# Schematic.net
KiCad netlist of a schematic drawn in EAGLE
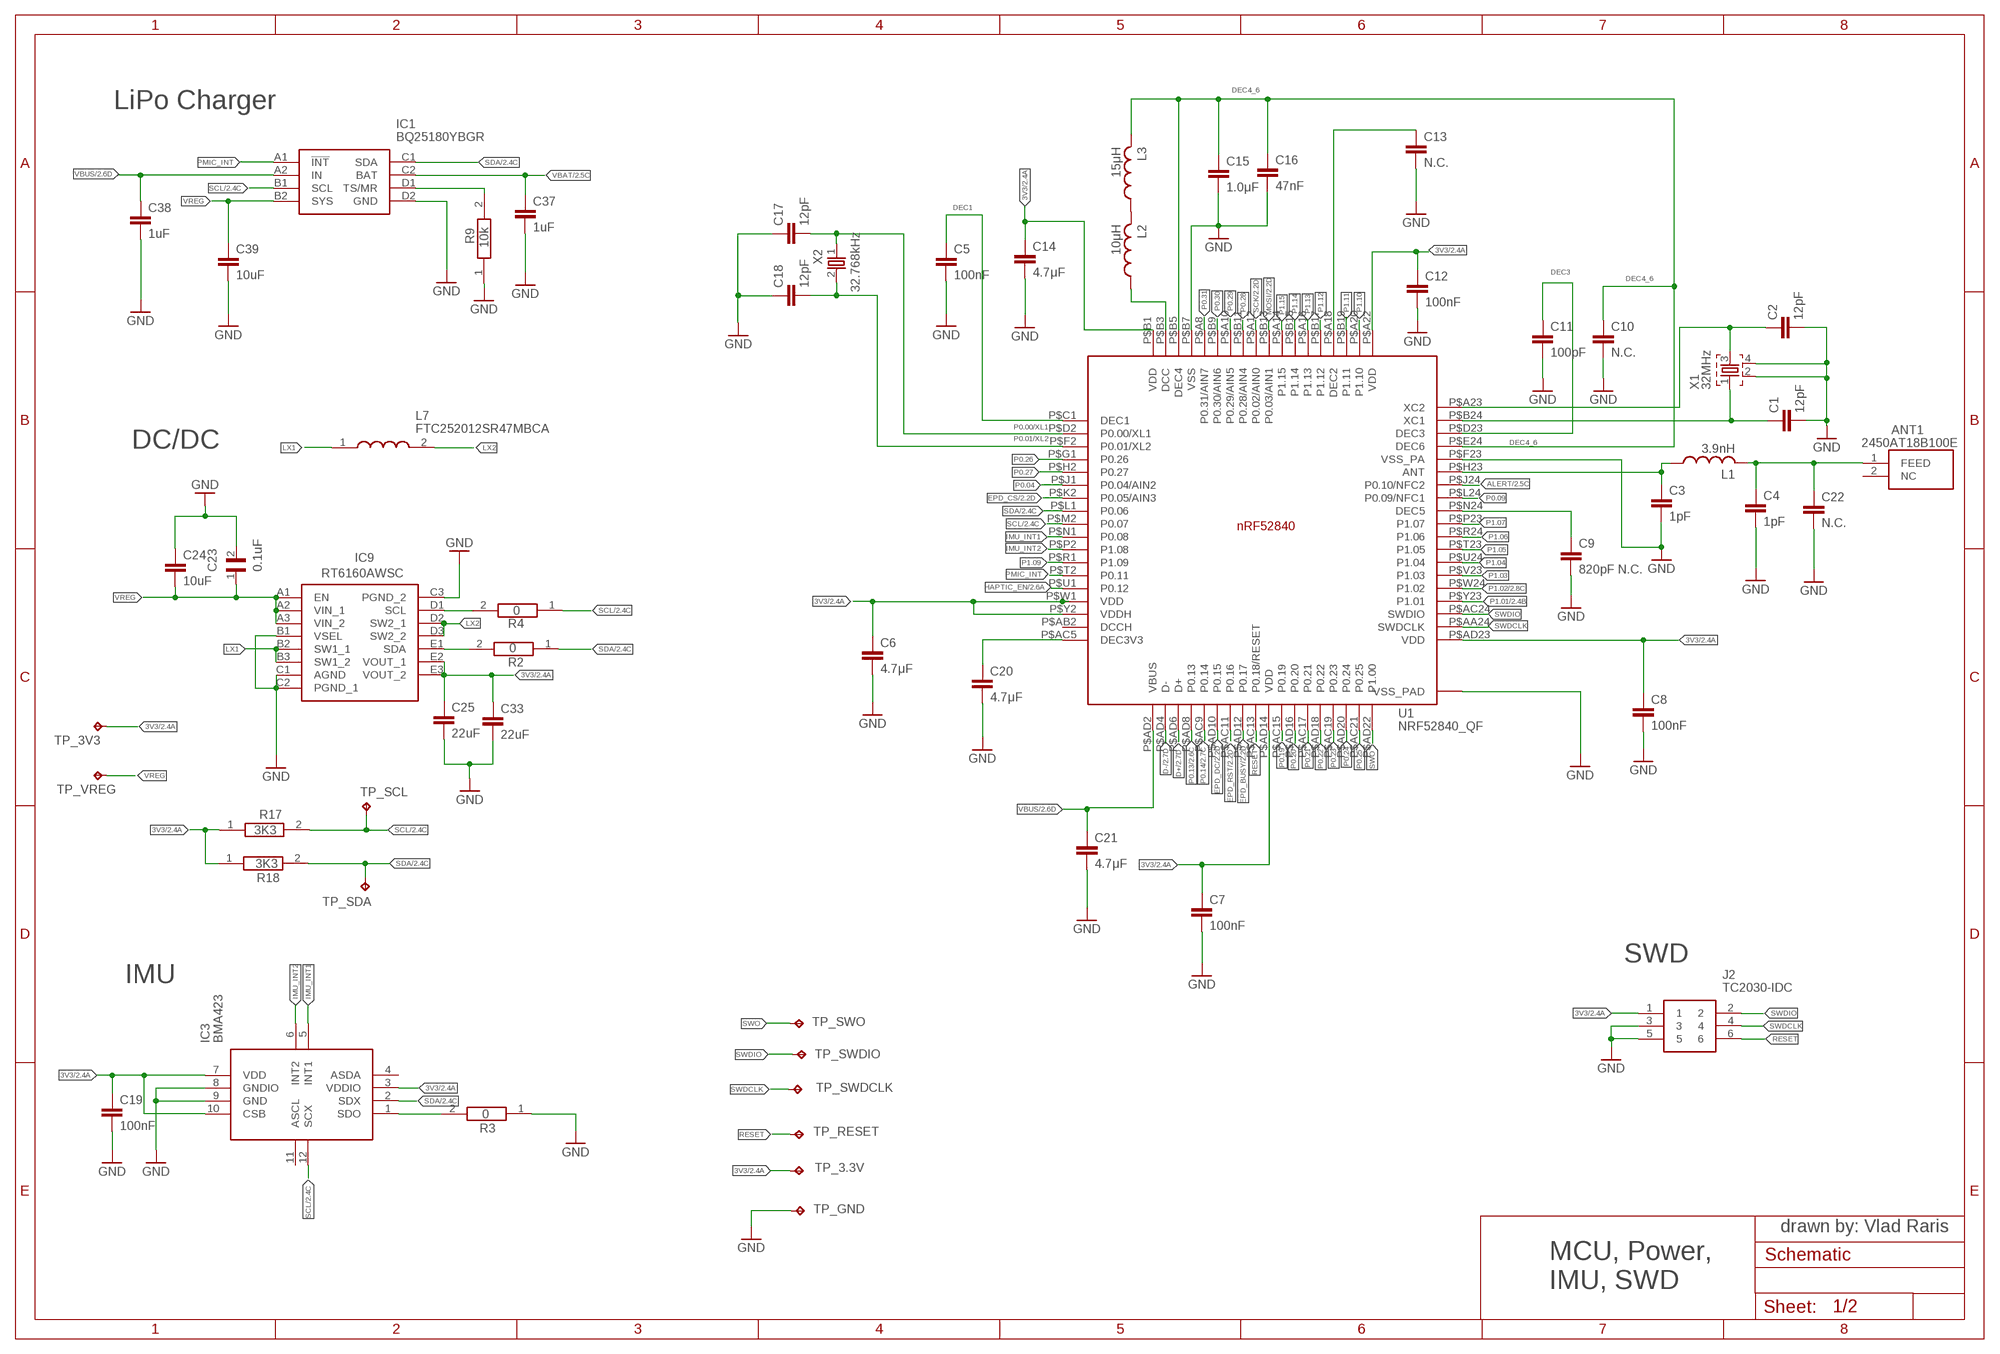
[diagram p0: schematic, sheet 1]
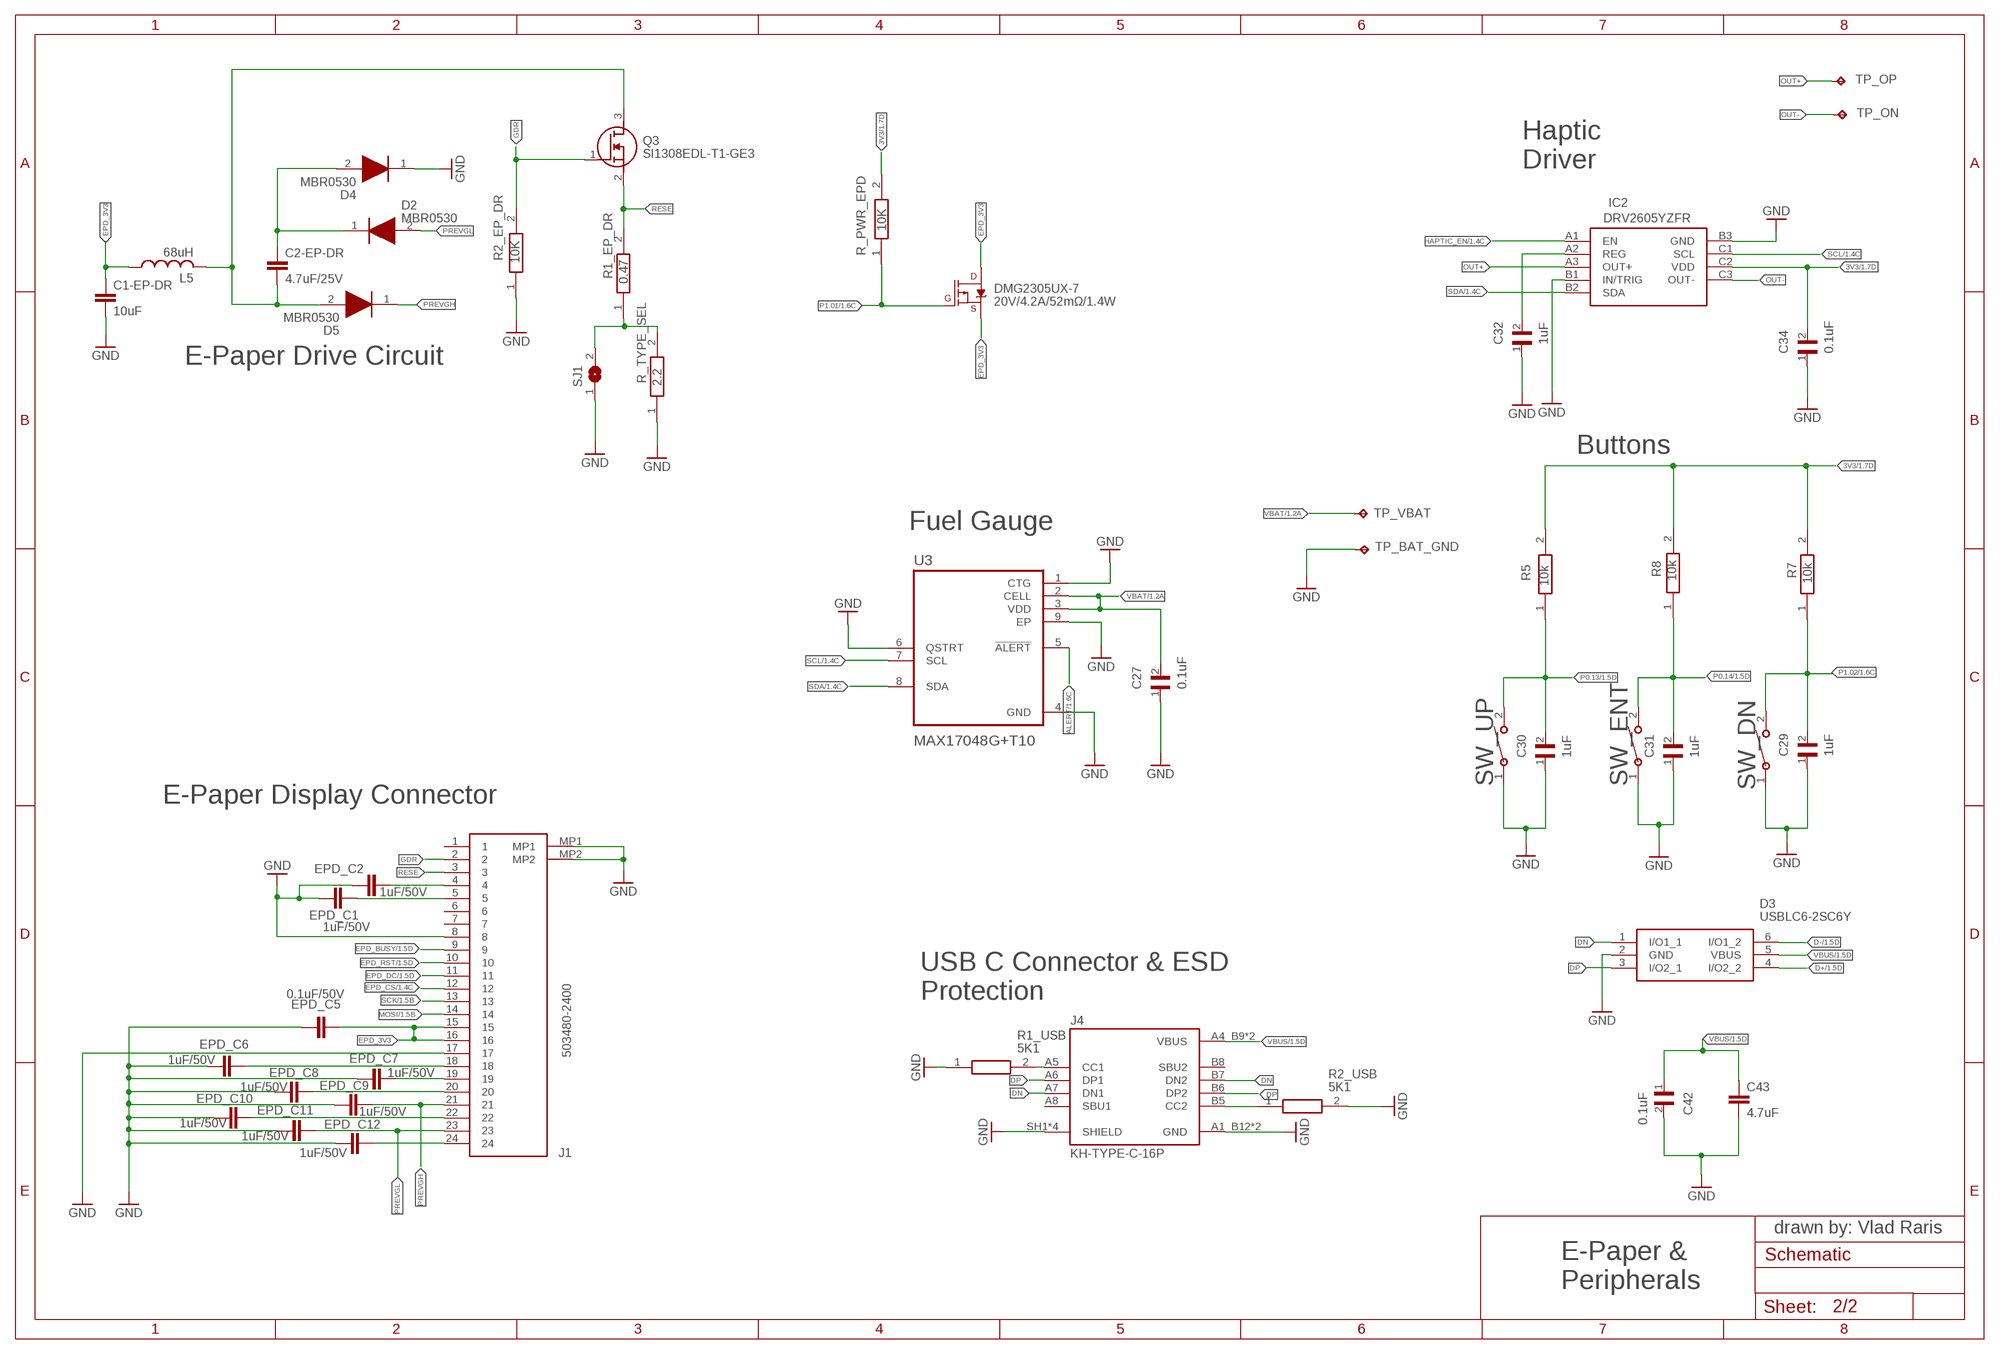
[diagram p1: schematic, sheet 2]

(export (version "E")
  (design (tool "Eeschema 10.0.6"))
  (components
    (comp (ref "C1-EP-DR")
      (value "10uF")
      (footprint "eagle-import:NORDIC_NRF_3_RESC0201_L")
      (libsource (lib "eagle-import") (part "NORDIC_NRF_3_CAPACITOR_0201_L"))
    )
    (comp (ref "C2-EP-DR")
      (value "4.7uF/25V")
      (footprint "eagle-import:PERFECT_0402_0402")
      (libsource (lib "eagle-import") (part "PERFECT_0402_CAP_0402"))
    )
    (comp (ref "C27")
      (value "0.1uF")
      (footprint "eagle-import:GRM011R60J152KE01L_2_CAPC0201X13N")
      (fields (field (name "MF") "Murata") (field (name "MP") "GRM011R60J152KE01L"))
      (libsource (lib "eagle-import") (part "GRM011R60J152KE01L_2_GRM011R60J152KE01L"))
    )
    (comp (ref "C29")
      (value "1uF")
      (footprint "eagle-import:GRM011R60J152KE01L_2_CAPC0201X13N")
      (fields (field (name "MF") "Murata") (field (name "MP") "GRM011R60J152KE01L"))
      (libsource (lib "eagle-import") (part "GRM011R60J152KE01L_2_GRM011R60J152KE01L"))
    )
    (comp (ref "C30")
      (value "1uF")
      (footprint "eagle-import:GRM011R60J152KE01L_2_CAPC0201X13N")
      (fields (field (name "MF") "Murata") (field (name "MP") "GRM011R60J152KE01L"))
      (libsource (lib "eagle-import") (part "GRM011R60J152KE01L_2_GRM011R60J152KE01L"))
    )
    (comp (ref "C31")
      (value "1uF")
      (footprint "eagle-import:GRM011R60J152KE01L_2_CAPC0201X13N")
      (fields (field (name "MF") "Murata") (field (name "MP") "GRM011R60J152KE01L"))
      (libsource (lib "eagle-import") (part "GRM011R60J152KE01L_2_GRM011R60J152KE01L"))
    )
    (comp (ref "C32")
      (value "1uF")
      (footprint "eagle-import:GRM011R60J152KE01L_2_CAPC0201X13N")
      (fields (field (name "MF") "Murata") (field (name "MP") "GRM011R60J152KE01L"))
      (libsource (lib "eagle-import") (part "GRM011R60J152KE01L_2_GRM011R60J152KE01L"))
    )
    (comp (ref "C34")
      (value "0.1uF")
      (footprint "eagle-import:GRM011R60J152KE01L_2_CAPC0201X13N")
      (fields (field (name "MF") "Murata") (field (name "MP") "GRM011R60J152KE01L"))
      (libsource (lib "eagle-import") (part "GRM011R60J152KE01L_2_GRM011R60J152KE01L"))
    )
    (comp (ref "C42")
      (value "0.1uF")
      (footprint "eagle-import:GRM011R60J152KE01L_2_CAPC0201X13N")
      (fields (field (name "MF") "Murata") (field (name "MP") "GRM011R60J152KE01L"))
      (libsource (lib "eagle-import") (part "GRM011R60J152KE01L_2_GRM011R60J152KE01L"))
    )
    (comp (ref "C43")
      (value "4.7uF")
      (footprint "eagle-import:PERFECT_0402_0402")
      (libsource (lib "eagle-import") (part "PERFECT_0402_CAP_0402"))
    )
    (comp (ref "D2")
      (value "MBR0530")
      (footprint "eagle-import:ESP32_C6_LIBRARY_5_SOD3716X135N")
      (fields (field (name "MF") "ON Semiconductor"))
      (libsource (lib "eagle-import") (part "ESP32_C6_LIBRARY_5_MBR0530"))
    )
    (comp (ref "D3")
      (value "USBLC6-2SC6Y")
      (footprint "eagle-import:ESP32_C6_LIBRARY_3_SOT95P280X145-6N")
      (fields (field (name "MF") "STMicroelectronics"))
      (libsource (lib "eagle-import") (part "ESP32_C6_LIBRARY_3_USBLC6-2SC6Y"))
    )
    (comp (ref "D4")
      (value "MBR0530")
      (footprint "eagle-import:ESP32_C6_LIBRARY_5_SOD3716X135N")
      (fields (field (name "MF") "ON Semiconductor"))
      (libsource (lib "eagle-import") (part "ESP32_C6_LIBRARY_5_MBR0530"))
    )
    (comp (ref "D5")
      (value "MBR0530")
      (footprint "eagle-import:ESP32_C6_LIBRARY_5_SOD3716X135N")
      (fields (field (name "MF") "ON Semiconductor"))
      (libsource (lib "eagle-import") (part "ESP32_C6_LIBRARY_5_MBR0530"))
    )
    (comp (ref "DMG2305UX-7")
      (value "20V/4.2A/52mΩ/1.4W")
      (footprint "eagle-import:ESP32_C6_LIBRARY_4_ESP32_C6_LIBRARY_4_ESP32_C6_LIBRARY_4_ESP32_C6_LIBRARY_4_ESP32_WROVER_SPARKFUN-DISCRETESEMI_SOT23-3")
      (libsource (lib "eagle-import") (part "ESP32_C6_LIBRARY_4_ESP32_WROVER_SPARKFUN-DISCRETESEMI_MOSFET_PCH-DMG2305UX-7"))
    )
    (comp (ref "EPD_C1")
      (value "1uF/50V")
      (footprint "eagle-import:PERFECT_0402_0402")
      (libsource (lib "eagle-import") (part "PERFECT_0402_CAP_0402"))
    )
    (comp (ref "EPD_C2")
      (value "1uF/50V")
      (footprint "eagle-import:PERFECT_0402_0402")
      (libsource (lib "eagle-import") (part "PERFECT_0402_CAP_0402"))
    )
    (comp (ref "EPD_C5")
      (value "0.1uF/50V")
      (footprint "eagle-import:PERFECT_0402_0402")
      (libsource (lib "eagle-import") (part "PERFECT_0402_CAP_0402"))
    )
    (comp (ref "EPD_C6")
      (value "1uF/50V")
      (footprint "eagle-import:PERFECT_0402_0402")
      (libsource (lib "eagle-import") (part "PERFECT_0402_CAP_0402"))
    )
    (comp (ref "EPD_C7")
      (value "1uF/50V")
      (footprint "eagle-import:PERFECT_0402_0402")
      (libsource (lib "eagle-import") (part "PERFECT_0402_CAP_0402"))
    )
    (comp (ref "EPD_C8")
      (value "1uF/50V")
      (footprint "eagle-import:PERFECT_0402_0402")
      (libsource (lib "eagle-import") (part "PERFECT_0402_CAP_0402"))
    )
    (comp (ref "EPD_C9")
      (value "1uF/50V")
      (footprint "eagle-import:PERFECT_0402_0402")
      (libsource (lib "eagle-import") (part "PERFECT_0402_CAP_0402"))
    )
    (comp (ref "EPD_C10")
      (value "1uF/50V")
      (footprint "eagle-import:PERFECT_0402_0402")
      (libsource (lib "eagle-import") (part "PERFECT_0402_CAP_0402"))
    )
    (comp (ref "EPD_C11")
      (value "1uF/50V")
      (footprint "eagle-import:PERFECT_0402_0402")
      (libsource (lib "eagle-import") (part "PERFECT_0402_CAP_0402"))
    )
    (comp (ref "EPD_C12")
      (value "1uF/50V")
      (footprint "eagle-import:PERFECT_0402_0402")
      (libsource (lib "eagle-import") (part "PERFECT_0402_CAP_0402"))
    )
    (comp (ref "IC2")
      (value "DRV2605YZFR")
      (footprint "eagle-import:DRV2605YZFR_BGA9C50P3X3_144X144X62")
      (libsource (lib "eagle-import") (part "DRV2605YZFR_DRV2605YZFR"))
    )
    (comp (ref "J1")
      (value "503480-2400")
      (footprint "eagle-import:503480-2400_5034802400")
      (fields (field (name "MOUSER_PART_NUMBER") "538-503480-2400"))
      (libsource (lib "eagle-import") (part "503480-2400_503480-2400"))
    )
    (comp (ref "J4")
      (value "KH-TYPE-C-16P")
      (footprint "eagle-import:KH-TYPE-C-16P_KINGHELM_KH-TYPE-C-16P")
      (fields (field (name "MF") "kinghelm"))
      (libsource (lib "eagle-import") (part "KH-TYPE-C-16P_KH-TYPE-C-16P"))
    )
    (comp (ref "L5")
      (value "68uH")
      (footprint "eagle-import:NORDIC_NRF_2_RESC0402_L")
      (libsource (lib "eagle-import") (part "NORDIC_NRF_2_INDUCTOR_0402_L"))
    )
    (comp (ref "Q3")
      (value "SI1308EDL-T1-GE3")
      (footprint "eagle-import:ESP32_C6_LIBRARY_6_SOT65P210X110-3N")
      (fields (field (name "MF") "Vishay Siliconix"))
      (libsource (lib "eagle-import") (part "ESP32_C6_LIBRARY_6_SI1308EDL-T1-GE3"))
    )
    (comp (ref "R1_EP_DR")
      (value "0.47")
      (footprint "eagle-import:CPF0201D7K68C1_0201")
      (libsource (lib "eagle-import") (part "CPF0201D7K68C1_CPF0201D7K68C1"))
    )
    (comp (ref "R1_USB")
      (value "5K1")
      (footprint "eagle-import:CPF0201D7K68C1_0201")
      (libsource (lib "eagle-import") (part "CPF0201D7K68C1_CPF0201D7K68C1"))
    )
    (comp (ref "R2_EP_DR")
      (value "10K")
      (footprint "eagle-import:CPF0201D7K68C1_0201")
      (libsource (lib "eagle-import") (part "CPF0201D7K68C1_CPF0201D7K68C1"))
    )
    (comp (ref "R2_USB")
      (value "5K1")
      (footprint "eagle-import:CPF0201D7K68C1_0201")
      (libsource (lib "eagle-import") (part "CPF0201D7K68C1_CPF0201D7K68C1"))
    )
    (comp (ref "R5")
      (value "10k")
      (footprint "eagle-import:CPF0201D7K68C1_0201")
      (libsource (lib "eagle-import") (part "CPF0201D7K68C1_CPF0201D7K68C1"))
    )
    (comp (ref "R7")
      (value "10k")
      (footprint "eagle-import:CPF0201D7K68C1_0201")
      (libsource (lib "eagle-import") (part "CPF0201D7K68C1_CPF0201D7K68C1"))
    )
    (comp (ref "R8")
      (value "10k")
      (footprint "eagle-import:CPF0201D7K68C1_0201")
      (libsource (lib "eagle-import") (part "CPF0201D7K68C1_CPF0201D7K68C1"))
    )
    (comp (ref "R_PWR_EPD")
      (value "10K")
      (footprint "eagle-import:CPF0201D7K68C1_0201")
      (libsource (lib "eagle-import") (part "CPF0201D7K68C1_CPF0201D7K68C1"))
    )
    (comp (ref "R_TYPE_SEL")
      (value "2.2")
      (footprint "eagle-import:CPF0201D7K68C1_0201")
      (libsource (lib "eagle-import") (part "CPF0201D7K68C1_CPF0201D7K68C1"))
    )
    (comp (ref "SJ1")
      (value "ESP32_C6_LIBRARY_7_JUMPER_SJ")
      (footprint "eagle-import:ESP32_C6_LIBRARY_7_JUMPER_SJ")
      (libsource (lib "eagle-import") (part "ESP32_C6_LIBRARY_7_JUMPER_SJ"))
    )
    (comp (ref "SW_DN")
      (value "2025-10-22_07-23-44_LIBRARY_EVP-AKE31ASW_EVP-AKE31A_PAN")
      (footprint "eagle-import:2025-10-22_07-23-44_LIBRARY_SW_EVP-AKE31A_PAN")
      (fields
        (field (name "MANUFACTURER_PART_NUMBER") "EVP-AKE31A")
        (field (name "COPYRIGHT") "Copyright (C) 2025 Ultra Librarian. All rights reserved.")
      )
      (libsource (lib "eagle-import") (part "2025-10-22_07-23-44_LIBRARY_EVP-AKE31ASW_EVP-AKE31A_PAN"))
    )
    (comp (ref "SW_ENT")
      (value "2025-10-22_07-23-44_LIBRARY_EVP-AKE31ASW_EVP-AKE31A_PAN")
      (footprint "eagle-import:2025-10-22_07-23-44_LIBRARY_SW_EVP-AKE31A_PAN")
      (fields
        (field (name "MANUFACTURER_PART_NUMBER") "EVP-AKE31A")
        (field (name "COPYRIGHT") "Copyright (C) 2025 Ultra Librarian. All rights reserved.")
      )
      (libsource (lib "eagle-import") (part "2025-10-22_07-23-44_LIBRARY_EVP-AKE31ASW_EVP-AKE31A_PAN"))
    )
    (comp (ref "SW_UP")
      (value "2025-10-22_07-23-44_LIBRARY_EVP-AKE31ASW_EVP-AKE31A_PAN")
      (footprint "eagle-import:2025-10-22_07-23-44_LIBRARY_SW_EVP-AKE31A_PAN")
      (fields
        (field (name "MANUFACTURER_PART_NUMBER") "EVP-AKE31A")
        (field (name "COPYRIGHT") "Copyright (C) 2025 Ultra Librarian. All rights reserved.")
      )
      (libsource (lib "eagle-import") (part "2025-10-22_07-23-44_LIBRARY_EVP-AKE31ASW_EVP-AKE31A_PAN"))
    )
    (comp (ref "TP_BAT_GND")
      (value "HECTOR_WATCH_1_TPTP20R")
      (footprint "eagle-import:HECTOR_WATCH_1_TP20R")
      (libsource (lib "eagle-import") (part "HECTOR_WATCH_1_TPTP20R"))
    )
    (comp (ref "TP_ON")
      (value "HECTOR_WATCH_1_TPTP20R")
      (footprint "eagle-import:HECTOR_WATCH_1_TP20R")
      (libsource (lib "eagle-import") (part "HECTOR_WATCH_1_TPTP20R"))
    )
    (comp (ref "TP_OP")
      (value "HECTOR_WATCH_1_TPTP20R")
      (footprint "eagle-import:HECTOR_WATCH_1_TP20R")
      (libsource (lib "eagle-import") (part "HECTOR_WATCH_1_TPTP20R"))
    )
    (comp (ref "TP_VBAT")
      (value "HECTOR_WATCH_1_TPTP20R")
      (footprint "eagle-import:HECTOR_WATCH_1_TP20R")
      (libsource (lib "eagle-import") (part "HECTOR_WATCH_1_TPTP20R"))
    )
    (comp (ref "U3")
      (value "MAX17048G+T10")
      (footprint "eagle-import:ESP32_C6_LIBRARY_SON50P200X200X80-9N")
      (fields (field (name "MF") "Analog Devices"))
      (libsource (lib "eagle-import") (part "ESP32_C6_LIBRARY_MAX17048G+T10"))
    )
    (comp (ref "ANT1")
      (value "2450AT18B100E")
      (footprint "eagle-import:2450AT18B100E_ANTC3216X140N")
      (fields (field (name "MOUSER_PART_NUMBER") "609-2450AT18B100E"))
      (libsource (lib "eagle-import") (part "2450AT18B100E_2450AT18B100E"))
    )
    (comp (ref "C1")
      (value "12pF")
      (footprint "eagle-import:NORDIC_NRF_3_RESC0201_L")
      (libsource (lib "eagle-import") (part "NORDIC_NRF_3_CAPACITOR_0201_L"))
    )
    (comp (ref "C2")
      (value "12pF")
      (footprint "eagle-import:NORDIC_NRF_3_RESC0201_L")
      (libsource (lib "eagle-import") (part "NORDIC_NRF_3_CAPACITOR_0201_L"))
    )
    (comp (ref "C3")
      (value "1pF")
      (footprint "eagle-import:NORDIC_NRF_3_RESC0201_L")
      (libsource (lib "eagle-import") (part "NORDIC_NRF_3_CAPACITOR_0201_L"))
    )
    (comp (ref "C4")
      (value "1pF")
      (footprint "eagle-import:NORDIC_NRF_3_RESC0201_L")
      (libsource (lib "eagle-import") (part "NORDIC_NRF_3_CAPACITOR_0201_L"))
    )
    (comp (ref "C5")
      (value "100nF")
      (footprint "eagle-import:NORDIC_NRF_3_RESC0201_L")
      (libsource (lib "eagle-import") (part "NORDIC_NRF_3_CAPACITOR_0201_L"))
    )
    (comp (ref "C6")
      (value "4.7μF")
      (footprint "eagle-import:PERFECT_0402_0402")
      (libsource (lib "eagle-import") (part "PERFECT_0402_CAP_0402"))
    )
    (comp (ref "C7")
      (value "100nF")
      (footprint "eagle-import:NORDIC_NRF_3_RESC0201_L")
      (libsource (lib "eagle-import") (part "NORDIC_NRF_3_CAPACITOR_0201_L"))
    )
    (comp (ref "C8")
      (value "100nF")
      (footprint "eagle-import:NORDIC_NRF_3_RESC0201_L")
      (libsource (lib "eagle-import") (part "NORDIC_NRF_3_CAPACITOR_0201_L"))
    )
    (comp (ref "C9")
      (value "820pF N.C.")
      (footprint "eagle-import:NORDIC_NRF_3_RESC0201_L")
      (libsource (lib "eagle-import") (part "NORDIC_NRF_3_CAPACITOR_0201_L"))
    )
    (comp (ref "C10")
      (value "N.C.")
      (footprint "eagle-import:NORDIC_NRF_3_RESC0201_L")
      (libsource (lib "eagle-import") (part "NORDIC_NRF_3_CAPACITOR_0201_L"))
    )
    (comp (ref "C11")
      (value "100pF")
      (footprint "eagle-import:NORDIC_NRF_3_RESC0201_L")
      (libsource (lib "eagle-import") (part "NORDIC_NRF_3_CAPACITOR_0201_L"))
    )
    (comp (ref "C12")
      (value "100nF")
      (footprint "eagle-import:NORDIC_NRF_3_RESC0201_L")
      (libsource (lib "eagle-import") (part "NORDIC_NRF_3_CAPACITOR_0201_L"))
    )
    (comp (ref "C13")
      (value "N.C.")
      (footprint "eagle-import:NORDIC_NRF_3_RESC0201_L")
      (libsource (lib "eagle-import") (part "NORDIC_NRF_3_CAPACITOR_0201_L"))
    )
    (comp (ref "C14")
      (value "4.7μF")
      (footprint "eagle-import:PERFECT_0402_0402")
      (libsource (lib "eagle-import") (part "PERFECT_0402_CAP_0402"))
    )
    (comp (ref "C15")
      (value "1.0μF")
      (footprint "eagle-import:PERFECT_0402_0402")
      (libsource (lib "eagle-import") (part "PERFECT_0402_CAP_0402"))
    )
    (comp (ref "C16")
      (value "47nF")
      (footprint "eagle-import:NORDIC_NRF_3_RESC0201_L")
      (libsource (lib "eagle-import") (part "NORDIC_NRF_3_CAPACITOR_0201_L"))
    )
    (comp (ref "C17")
      (value "12pF")
      (footprint "eagle-import:NORDIC_NRF_3_RESC0201_L")
      (libsource (lib "eagle-import") (part "NORDIC_NRF_3_CAPACITOR_0201_L"))
    )
    (comp (ref "C18")
      (value "12pF")
      (footprint "eagle-import:NORDIC_NRF_3_RESC0201_L")
      (libsource (lib "eagle-import") (part "NORDIC_NRF_3_CAPACITOR_0201_L"))
    )
    (comp (ref "C19")
      (value "100nF")
      (footprint "eagle-import:PERFECT_0402_0402")
      (libsource (lib "eagle-import") (part "PERFECT_0402_CAP_0402"))
    )
    (comp (ref "C20")
      (value "4.7μF")
      (footprint "eagle-import:PERFECT_0402_0402")
      (libsource (lib "eagle-import") (part "PERFECT_0402_CAP_0402"))
    )
    (comp (ref "C21")
      (value "4.7μF")
      (footprint "eagle-import:PERFECT_0402_0402")
      (libsource (lib "eagle-import") (part "PERFECT_0402_CAP_0402"))
    )
    (comp (ref "C22")
      (value "N.C.")
      (footprint "eagle-import:NORDIC_NRF_3_RESC0201_L")
      (libsource (lib "eagle-import") (part "NORDIC_NRF_3_CAPACITOR_0201_L"))
    )
    (comp (ref "C23")
      (value "0.1uF")
      (footprint "eagle-import:GRM011R60J152KE01L_1_0201")
      (libsource (lib "eagle-import") (part "GRM011R60J152KE01L_1_GRM011R60J152KE01L"))
    )
    (comp (ref "C24")
      (value "10uF")
      (footprint "eagle-import:PERFECT_0402_0402")
      (libsource (lib "eagle-import") (part "PERFECT_0402_CAP_0402"))
    )
    (comp (ref "C25")
      (value "22uF")
      (footprint "eagle-import:PERFECT_0402_0402")
      (libsource (lib "eagle-import") (part "PERFECT_0402_CAP_0402"))
    )
    (comp (ref "C33")
      (value "22uF")
      (footprint "eagle-import:PERFECT_0402_0402")
      (libsource (lib "eagle-import") (part "PERFECT_0402_CAP_0402"))
    )
    (comp (ref "C37")
      (value "1uF")
      (footprint "eagle-import:PERFECT_0402_0402")
      (libsource (lib "eagle-import") (part "PERFECT_0402_CAP_0402"))
    )
    (comp (ref "C38")
      (value "1uF")
      (footprint "eagle-import:PERFECT_0402_0402")
      (libsource (lib "eagle-import") (part "PERFECT_0402_CAP_0402"))
    )
    (comp (ref "C39")
      (value "10uF")
      (footprint "eagle-import:PERFECT_0402_0402")
      (libsource (lib "eagle-import") (part "PERFECT_0402_CAP_0402"))
    )
    (comp (ref "IC1")
      (value "BQ25180YBGR")
      (footprint "eagle-import:BQ25180YBGR_BGA8C40P2X4_100X155X50")
      (fields (field (name "MOUSER_PART_NUMBER") "595-BQ25180YBGR"))
      (libsource (lib "eagle-import") (part "BQ25180YBGR_BQ25180YBGR"))
    )
    (comp (ref "IC3")
      (value "BMA423")
      (footprint "eagle-import:BMA423_BMA423")
      (fields (field (name "MOUSER_PART_NUMBER") "262-BMA423"))
      (libsource (lib "eagle-import") (part "BMA423_BMA423"))
    )
    (comp (ref "IC9")
      (value "RT6160AWSC")
      (footprint "eagle-import:RT6160AWSC_BGA15C40P3X5_140X230X60")
      (fields (field (name "MOUSER_PART_NUMBER") "835-RT6160AWSC"))
      (libsource (lib "eagle-import") (part "RT6160AWSC_RT6160AWSC"))
    )
    (comp (ref "J2")
      (value "TC2030-IDC")
      (footprint "eagle-import:TC2030-IDC_TC2030IDC")
      (libsource (lib "eagle-import") (part "TC2030-IDC_TC2030-IDC"))
    )
    (comp (ref "L1")
      (value "3.9nH")
      (footprint "eagle-import:NORDIC_NRF_2_RESC0402_L")
      (libsource (lib "eagle-import") (part "NORDIC_NRF_2_INDUCTOR_0402_L"))
    )
    (comp (ref "L2")
      (value "10μH")
      (footprint "eagle-import:NORDIC_NRF_2_RESC0402_L")
      (libsource (lib "eagle-import") (part "NORDIC_NRF_2_INDUCTOR_0402_L"))
    )
    (comp (ref "L3")
      (value "15μH")
      (footprint "eagle-import:NORDIC_NRF_2_RESC0402_L")
      (libsource (lib "eagle-import") (part "NORDIC_NRF_2_INDUCTOR_0402_L"))
    )
    (comp (ref "L7")
      (value "FTC252012SR47MBCA")
      (footprint "eagle-import:MLP2016SR47MT0S1_INDC2016X100N")
      (libsource (lib "eagle-import") (part "MLP2016SR47MT0S1_FTC252012SR47MBCA"))
    )
    (comp (ref "R2")
      (value "0")
      (footprint "eagle-import:CPF0201D7K68C1_0201")
      (libsource (lib "eagle-import") (part "CPF0201D7K68C1_CPF0201D7K68C1"))
    )
    (comp (ref "R3")
      (value "0")
      (footprint "eagle-import:CPF0201D7K68C1_0201")
      (libsource (lib "eagle-import") (part "CPF0201D7K68C1_CPF0201D7K68C1"))
    )
    (comp (ref "R4")
      (value "0")
      (footprint "eagle-import:CPF0201D7K68C1_0201")
      (libsource (lib "eagle-import") (part "CPF0201D7K68C1_CPF0201D7K68C1"))
    )
    (comp (ref "R9")
      (value "10k")
      (footprint "eagle-import:CPF0201D7K68C1_0201")
      (libsource (lib "eagle-import") (part "CPF0201D7K68C1_CPF0201D7K68C1"))
    )
    (comp (ref "R17")
      (value "3K3")
      (footprint "eagle-import:CPF0201D7K68C1_0201")
      (libsource (lib "eagle-import") (part "CPF0201D7K68C1_CPF0201D7K68C1"))
    )
    (comp (ref "R18")
      (value "3K3")
      (footprint "eagle-import:CPF0201D7K68C1_0201")
      (libsource (lib "eagle-import") (part "CPF0201D7K68C1_CPF0201D7K68C1"))
    )
    (comp (ref "TP_3.3V")
      (value "HECTOR_WATCH_1_TPTP20R")
      (footprint "eagle-import:HECTOR_WATCH_1_TP20R")
      (libsource (lib "eagle-import") (part "HECTOR_WATCH_1_TPTP20R"))
    )
    (comp (ref "TP_3V3")
      (value "HECTOR_WATCH_1_TPTP20R")
      (footprint "eagle-import:HECTOR_WATCH_1_TP20R")
      (libsource (lib "eagle-import") (part "HECTOR_WATCH_1_TPTP20R"))
    )
    (comp (ref "TP_GND")
      (value "HECTOR_WATCH_1_TPTP20R")
      (footprint "eagle-import:HECTOR_WATCH_1_TP20R")
      (libsource (lib "eagle-import") (part "HECTOR_WATCH_1_TPTP20R"))
    )
    (comp (ref "TP_RESET")
      (value "HECTOR_WATCH_1_TPTP20R")
      (footprint "eagle-import:HECTOR_WATCH_1_TP20R")
      (libsource (lib "eagle-import") (part "HECTOR_WATCH_1_TPTP20R"))
    )
    (comp (ref "TP_SCL")
      (value "HECTOR_WATCH_1_TPTP20R")
      (footprint "eagle-import:HECTOR_WATCH_1_TP20R")
      (libsource (lib "eagle-import") (part "HECTOR_WATCH_1_TPTP20R"))
    )
    (comp (ref "TP_SDA")
      (value "HECTOR_WATCH_1_TPTP20R")
      (footprint "eagle-import:HECTOR_WATCH_1_TP20R")
      (libsource (lib "eagle-import") (part "HECTOR_WATCH_1_TPTP20R"))
    )
    (comp (ref "TP_SWDCLK")
      (value "HECTOR_WATCH_1_TPTP20R")
      (footprint "eagle-import:HECTOR_WATCH_1_TP20R")
      (libsource (lib "eagle-import") (part "HECTOR_WATCH_1_TPTP20R"))
    )
    (comp (ref "TP_SWDIO")
      (value "HECTOR_WATCH_1_TPTP20R")
      (footprint "eagle-import:HECTOR_WATCH_1_TP20R")
      (libsource (lib "eagle-import") (part "HECTOR_WATCH_1_TPTP20R"))
    )
    (comp (ref "TP_SWO")
      (value "HECTOR_WATCH_1_TPTP20R")
      (footprint "eagle-import:HECTOR_WATCH_1_TP20R")
      (libsource (lib "eagle-import") (part "HECTOR_WATCH_1_TPTP20R"))
    )
    (comp (ref "TP_VREG")
      (value "HECTOR_WATCH_1_TPTP20R")
      (footprint "eagle-import:HECTOR_WATCH_1_TP20R")
      (libsource (lib "eagle-import") (part "HECTOR_WATCH_1_TPTP20R"))
    )
    (comp (ref "U1")
      (value "NRF52840_QF")
      (footprint "eagle-import:NORDIC_NRF_4_AQFN50P700X700X85_HS-74N")
      (libsource (lib "eagle-import") (part "NORDIC_NRF_4_NRF52840_QF"))
    )
    (comp (ref "X1")
      (value "32MHz")
      (footprint "eagle-import:NORDIC_NRF_BT-XTAL_2016_N")
      (libsource (lib "eagle-import") (part "NORDIC_NRF_XTAL_32MHZ"))
    )
    (comp (ref "X2")
      (value "32.768kHz")
      (footprint "eagle-import:NORDIC_NRF_1_XTAL_3215_N")
      (libsource (lib "eagle-import") (part "NORDIC_NRF_1_XTAL_32KHZ"))
    )
  )
  (nets
    (net (code "1") (name "3V3{slash}1.7D") (class "Default")
      (node (ref "C34") (pin "2") (pinfunction "2_2") (pintype "passive"))
      (node (ref "IC2") (pin "C2") (pinfunction "VDD_C2") (pintype "bidirectional"))
      (node (ref "R5") (pin "2") (pinfunction "2_2") (pintype "bidirectional"))
      (node (ref "R7") (pin "2") (pinfunction "2_2") (pintype "bidirectional"))
      (node (ref "R8") (pin "2") (pinfunction "2_2") (pintype "bidirectional"))
      (node (ref "R_PWR_EPD") (pin "2") (pinfunction "2_2") (pintype "bidirectional"))
    )
    (net (code "2") (name "3V3{slash}2.4A") (class "Default")
      (node (ref "C12") (pin "1") (pinfunction "1_1") (pintype "passive"))
      (node (ref "C14") (pin "1") (pinfunction "1_1") (pintype "passive"))
      (node (ref "C19") (pin "1") (pinfunction "1_1") (pintype "passive"))
      (node (ref "C25") (pin "1") (pinfunction "1_1") (pintype "passive"))
      (node (ref "C33") (pin "1") (pinfunction "1_1") (pintype "passive"))
      (node (ref "C6") (pin "1") (pinfunction "1_1") (pintype "passive"))
      (node (ref "C7") (pin "1") (pinfunction "1_1") (pintype "passive"))
      (node (ref "C8") (pin "1") (pinfunction "1_1") (pintype "passive"))
      (node (ref "IC3") (pin "10") (pinfunction "CSB_10") (pintype "bidirectional"))
      (node (ref "IC3") (pin "3") (pinfunction "VDDIO_3") (pintype "bidirectional"))
      (node (ref "IC3") (pin "7") (pinfunction "VDD_7") (pintype "bidirectional"))
      (node (ref "IC9") (pin "E2") (pinfunction "VOUT_1_E2") (pintype "bidirectional"))
      (node (ref "IC9") (pin "E3") (pinfunction "VOUT_2_E3") (pintype "bidirectional"))
      (node (ref "J2") (pin "1") (pinfunction "1_1") (pintype "bidirectional"))
      (node (ref "R17") (pin "1") (pinfunction "1_1") (pintype "bidirectional"))
      (node (ref "R18") (pin "1") (pinfunction "1_1") (pintype "bidirectional"))
      (node (ref "TP_3.3V") (pin "TP") (pinfunction "TP_TP") (pintype "input"))
      (node (ref "TP_3V3") (pin "TP") (pinfunction "TP_TP") (pintype "input"))
      (node (ref "U1") (pin "P$A22") (pinfunction "VDD_P$A22") (pintype "power_in"))
      (node (ref "U1") (pin "P$AD14") (pinfunction "VDD_P$AD14") (pintype "power_in"))
      (node (ref "U1") (pin "P$AD23") (pinfunction "VDD_P$AD23") (pintype "power_in"))
      (node (ref "U1") (pin "P$B1") (pinfunction "VDD_P$B1") (pintype "power_in"))
      (node (ref "U1") (pin "P$W1") (pinfunction "VDD_P$W1") (pintype "power_in"))
      (node (ref "U1") (pin "P$Y2") (pinfunction "VDDH_P$Y2") (pintype "power_in"))
    )
    (net (code "3") (name "ALERT{slash}1.6C") (class "Default")
      (node (ref "U3") (pin "5") (pinfunction "~{ALERT}_5") (pintype "output"))
    )
    (net (code "4") (name "ALERT{slash}2.5C") (class "Default")
      (node (ref "U1") (pin "P$J24") (pinfunction "P0.10/NFC2_P$J24") (pintype "bidirectional"))
    )
    (net (code "5") (name "D+{slash}1.5D") (class "Default")
      (node (ref "D3") (pin "4") (pinfunction "I/O2_2_4") (pintype "bidirectional"))
    )
    (net (code "6") (name "D+{slash}2.7D") (class "Default")
      (node (ref "U1") (pin "P$AD6") (pinfunction "D+_P$AD6") (pintype "bidirectional"))
    )
    (net (code "7") (name "D-{slash}1.5D") (class "Default")
      (node (ref "D3") (pin "6") (pinfunction "I/O1_2_6") (pintype "bidirectional"))
    )
    (net (code "8") (name "D-{slash}2.7D") (class "Default")
      (node (ref "U1") (pin "P$AD4") (pinfunction "D-_P$AD4") (pintype "bidirectional"))
    )
    (net (code "9") (name "DEC1") (class "Default")
      (node (ref "C5") (pin "1") (pinfunction "1_1") (pintype "passive"))
      (node (ref "U1") (pin "P$C1") (pinfunction "DEC1_P$C1") (pintype "power_in"))
    )
    (net (code "10") (name "DEC3") (class "Default")
      (node (ref "C11") (pin "1") (pinfunction "1_1") (pintype "passive"))
      (node (ref "U1") (pin "P$D23") (pinfunction "DEC3_P$D23") (pintype "bidirectional"))
    )
    (net (code "11") (name "DEC4_6") (class "Default")
      (node (ref "C10") (pin "1") (pinfunction "1_1") (pintype "passive"))
      (node (ref "C15") (pin "1") (pinfunction "1_1") (pintype "passive"))
      (node (ref "C16") (pin "1") (pinfunction "1_1") (pintype "passive"))
      (node (ref "L3") (pin "2") (pinfunction "2_2") (pintype "passive"))
      (node (ref "U1") (pin "P$B5") (pinfunction "DEC4_P$B5") (pintype "power_in"))
      (node (ref "U1") (pin "P$E24") (pinfunction "DEC6_P$E24") (pintype "bidirectional"))
    )
    (net (code "12") (name "DN") (class "Default")
      (node (ref "D3") (pin "1") (pinfunction "I/O1_1_1") (pintype "bidirectional"))
      (node (ref "J4") (pin "A7") (pinfunction "DN1_A7") (pintype "bidirectional"))
      (node (ref "J4") (pin "B7") (pinfunction "DN2_B7") (pintype "bidirectional"))
    )
    (net (code "13") (name "DP") (class "Default")
      (node (ref "D3") (pin "3") (pinfunction "I/O2_1_3") (pintype "bidirectional"))
      (node (ref "J4") (pin "A6") (pinfunction "DP1_A6") (pintype "bidirectional"))
      (node (ref "J4") (pin "B6") (pinfunction "DP2_B6") (pintype "bidirectional"))
    )
    (net (code "14") (name "EPD_3V3") (class "Default")
      (node (ref "C1-EP-DR") (pin "1") (pinfunction "1_1") (pintype "passive"))
      (node (ref "DMG2305UX-7") (pin "2") (pinfunction "S_2") (pintype "bidirectional"))
      (node (ref "DMG2305UX-7") (pin "3") (pinfunction "D_3") (pintype "bidirectional"))
      (node (ref "EPD_C5") (pin "2") (pinfunction "2_2") (pintype "passive"))
      (node (ref "J1") (pin "15") (pinfunction "15_15") (pintype "bidirectional"))
      (node (ref "J1") (pin "16") (pinfunction "16_16") (pintype "bidirectional"))
      (node (ref "L5") (pin "1") (pinfunction "1_1") (pintype "passive"))
    )
    (net (code "15") (name "EPD_BUSY{slash}1.5D") (class "Default")
      (node (ref "J1") (pin "9") (pinfunction "9_9") (pintype "bidirectional"))
    )
    (net (code "16") (name "EPD_BUSY{slash}2.2D") (class "Default")
      (node (ref "U1") (pin "P$AD12") (pinfunction "P0.17_P$AD12") (pintype "bidirectional"))
    )
    (net (code "17") (name "EPD_CS{slash}1.4C") (class "Default")
      (node (ref "J1") (pin "12") (pinfunction "12_12") (pintype "bidirectional"))
    )
    (net (code "18") (name "EPD_CS{slash}2.2D") (class "Default")
      (node (ref "U1") (pin "P$K2") (pinfunction "P0.05/AIN3_P$K2") (pintype "bidirectional"))
    )
    (net (code "19") (name "EPD_DC{slash}1.5D") (class "Default")
      (node (ref "J1") (pin "11") (pinfunction "11_11") (pintype "bidirectional"))
    )
    (net (code "20") (name "EPD_DC{slash}2.2D") (class "Default")
      (node (ref "U1") (pin "P$AD10") (pinfunction "P0.15_P$AD10") (pintype "bidirectional"))
    )
    (net (code "21") (name "EPD_RST{slash}1.5D") (class "Default")
      (node (ref "J1") (pin "10") (pinfunction "10_10") (pintype "bidirectional"))
    )
    (net (code "22") (name "EPD_RST{slash}2.2D") (class "Default")
      (node (ref "U1") (pin "P$AC11") (pinfunction "P0.16_P$AC11") (pintype "bidirectional"))
    )
    (net (code "23") (name "GDR") (class "Default")
      (node (ref "J1") (pin "2") (pinfunction "2_2") (pintype "bidirectional"))
      (node (ref "Q3") (pin "1") (pinfunction "G_1") (pintype "bidirectional"))
      (node (ref "R2_EP_DR") (pin "2") (pinfunction "2_2") (pintype "bidirectional"))
    )
    (net (code "24") (name "GND") (class "Default")
      (node (ref "C1") (pin "2") (pinfunction "2_2") (pintype "passive"))
      (node (ref "C1-EP-DR") (pin "2") (pinfunction "2_2") (pintype "passive"))
      (node (ref "C10") (pin "2") (pinfunction "2_2") (pintype "passive"))
      (node (ref "C11") (pin "2") (pinfunction "2_2") (pintype "passive"))
      (node (ref "C12") (pin "2") (pinfunction "2_2") (pintype "passive"))
      (node (ref "C13") (pin "2") (pinfunction "2_2") (pintype "passive"))
      (node (ref "C14") (pin "2") (pinfunction "2_2") (pintype "passive"))
      (node (ref "C15") (pin "2") (pinfunction "2_2") (pintype "passive"))
      (node (ref "C16") (pin "2") (pinfunction "2_2") (pintype "passive"))
      (node (ref "C17") (pin "1") (pinfunction "1_1") (pintype "passive"))
      (node (ref "C18") (pin "1") (pinfunction "1_1") (pintype "passive"))
      (node (ref "C19") (pin "2") (pinfunction "2_2") (pintype "passive"))
      (node (ref "C2") (pin "2") (pinfunction "2_2") (pintype "passive"))
      (node (ref "C20") (pin "2") (pinfunction "2_2") (pintype "passive"))
      (node (ref "C21") (pin "2") (pinfunction "2_2") (pintype "passive"))
      (node (ref "C22") (pin "2") (pinfunction "2_2") (pintype "passive"))
      (node (ref "C23") (pin "2") (pinfunction "2_2") (pintype "passive"))
      (node (ref "C24") (pin "1") (pinfunction "1_1") (pintype "passive"))
      (node (ref "C25") (pin "2") (pinfunction "2_2") (pintype "passive"))
      (node (ref "C27") (pin "1") (pinfunction "1_1") (pintype "passive"))
      (node (ref "C29") (pin "1") (pinfunction "1_1") (pintype "passive"))
      (node (ref "C3") (pin "2") (pinfunction "2_2") (pintype "passive"))
      (node (ref "C30") (pin "1") (pinfunction "1_1") (pintype "passive"))
      (node (ref "C31") (pin "1") (pinfunction "1_1") (pintype "passive"))
      (node (ref "C32") (pin "1") (pinfunction "1_1") (pintype "passive"))
      (node (ref "C33") (pin "2") (pinfunction "2_2") (pintype "passive"))
      (node (ref "C34") (pin "1") (pinfunction "1_1") (pintype "passive"))
      (node (ref "C37") (pin "2") (pinfunction "2_2") (pintype "passive"))
      (node (ref "C38") (pin "2") (pinfunction "2_2") (pintype "passive"))
      (node (ref "C39") (pin "2") (pinfunction "2_2") (pintype "passive"))
      (node (ref "C4") (pin "2") (pinfunction "2_2") (pintype "passive"))
      (node (ref "C42") (pin "2") (pinfunction "2_2") (pintype "passive"))
      (node (ref "C43") (pin "2") (pinfunction "2_2") (pintype "passive"))
      (node (ref "C5") (pin "2") (pinfunction "2_2") (pintype "passive"))
      (node (ref "C6") (pin "2") (pinfunction "2_2") (pintype "passive"))
      (node (ref "C7") (pin "2") (pinfunction "2_2") (pintype "passive"))
      (node (ref "C8") (pin "2") (pinfunction "2_2") (pintype "passive"))
      (node (ref "C9") (pin "2") (pinfunction "2_2") (pintype "passive"))
      (node (ref "D3") (pin "2") (pinfunction "GND_2") (pintype "bidirectional"))
      (node (ref "D4") (pin "1") (pinfunction "K_1") (pintype "bidirectional"))
      (node (ref "EPD_C1") (pin "1") (pinfunction "1_1") (pintype "passive"))
      (node (ref "EPD_C10") (pin "1") (pinfunction "1_1") (pintype "passive"))
      (node (ref "EPD_C11") (pin "1") (pinfunction "1_1") (pintype "passive"))
      (node (ref "EPD_C12") (pin "1") (pinfunction "1_1") (pintype "passive"))
      (node (ref "EPD_C2") (pin "1") (pinfunction "1_1") (pintype "passive"))
      (node (ref "EPD_C5") (pin "1") (pinfunction "1_1") (pintype "passive"))
      (node (ref "EPD_C6") (pin "1") (pinfunction "1_1") (pintype "passive"))
      (node (ref "EPD_C7") (pin "1") (pinfunction "1_1") (pintype "passive"))
      (node (ref "EPD_C8") (pin "1") (pinfunction "1_1") (pintype "passive"))
      (node (ref "EPD_C9") (pin "1") (pinfunction "1_1") (pintype "passive"))
      (node (ref "IC1") (pin "D2") (pinfunction "GND_D2") (pintype "bidirectional"))
      (node (ref "IC2") (pin "B1") (pinfunction "IN/TRIG_B1") (pintype "bidirectional"))
      (node (ref "IC2") (pin "B3") (pinfunction "GND_B3") (pintype "bidirectional"))
      (node (ref "IC3") (pin "8") (pinfunction "GNDIO_8") (pintype "bidirectional"))
      (node (ref "IC3") (pin "9") (pinfunction "GND_9") (pintype "bidirectional"))
      (node (ref "IC9") (pin "B1") (pinfunction "VSEL_B1") (pintype "bidirectional"))
      (node (ref "IC9") (pin "C1") (pinfunction "AGND_C1") (pintype "bidirectional"))
      (node (ref "IC9") (pin "C2") (pinfunction "PGND_1_C2") (pintype "bidirectional"))
      (node (ref "IC9") (pin "C3") (pinfunction "PGND_2_C3") (pintype "bidirectional"))
      (node (ref "J1") (pin "17") (pinfunction "17_17") (pintype "bidirectional"))
      (node (ref "J1") (pin "8") (pinfunction "8_8") (pintype "bidirectional"))
      (node (ref "J1") (pin "MP1") (pinfunction "MP1_MP1") (pintype "bidirectional"))
      (node (ref "J1") (pin "MP2") (pinfunction "MP2_MP2") (pintype "bidirectional"))
      (node (ref "J2") (pin "3") (pinfunction "3_3") (pintype "bidirectional"))
      (node (ref "J2") (pin "5") (pinfunction "5_5") (pintype "bidirectional"))
      (node (ref "J4") (pin "A12_B1") (pinfunction "GND_A12_B1") (pintype "power_in"))
      (node (ref "J4") (pin "A1_B12") (pinfunction "GND_A1_B12") (pintype "power_in"))
      (node (ref "J4") (pin "SH1") (pinfunction "SHIELD_SH1") (pintype "passive"))
      (node (ref "J4") (pin "SH2") (pinfunction "SHIELD_SH2") (pintype "passive"))
      (node (ref "J4") (pin "SH3") (pinfunction "SHIELD_SH3") (pintype "passive"))
      (node (ref "J4") (pin "SH4") (pinfunction "SHIELD_SH4") (pintype "passive"))
      (node (ref "R1_USB") (pin "1") (pinfunction "1_1") (pintype "bidirectional"))
      (node (ref "R2_EP_DR") (pin "1") (pinfunction "1_1") (pintype "bidirectional"))
      (node (ref "R2_USB") (pin "2") (pinfunction "2_2") (pintype "bidirectional"))
      (node (ref "R3") (pin "1") (pinfunction "1_1") (pintype "bidirectional"))
      (node (ref "R9") (pin "1") (pinfunction "1_1") (pintype "bidirectional"))
      (node (ref "R_TYPE_SEL") (pin "1") (pinfunction "1_1") (pintype "bidirectional"))
      (node (ref "SJ1") (pin "1") (pinfunction "1_1") (pintype "passive"))
      (node (ref "SW_DN") (pin "1") (pinfunction "1_1") (pintype "passive"))
      (node (ref "SW_ENT") (pin "1") (pinfunction "1_1") (pintype "passive"))
      (node (ref "SW_UP") (pin "1") (pinfunction "1_1") (pintype "passive"))
      (node (ref "TP_BAT_GND") (pin "TP") (pinfunction "TP_TP") (pintype "input"))
      (node (ref "TP_GND") (pin "TP") (pinfunction "TP_TP") (pintype "input"))
      (node (ref "U1") (pin "P$74") (pinfunction "VSS_PAD_P$74") (pintype "bidirectional"))
      (node (ref "U1") (pin "P$75") (pinfunction "VSS_PAD_P$75") (pintype "bidirectional"))
      (node (ref "U1") (pin "P$76") (pinfunction "VSS_PAD_P$76") (pintype "bidirectional"))
      (node (ref "U1") (pin "P$77") (pinfunction "VSS_PAD_P$77") (pintype "bidirectional"))
      (node (ref "U1") (pin "P$78") (pinfunction "VSS_PAD_P$78") (pintype "bidirectional"))
      (node (ref "U1") (pin "P$79") (pinfunction "VSS_PAD_P$79") (pintype "bidirectional"))
      (node (ref "U1") (pin "P$80") (pinfunction "VSS_PAD_P$80") (pintype "bidirectional"))
      (node (ref "U1") (pin "P$81") (pinfunction "VSS_PAD_P$81") (pintype "bidirectional"))
      (node (ref "U1") (pin "P$82") (pinfunction "VSS_PAD_P$82") (pintype "bidirectional"))
      (node (ref "U1") (pin "P$83") (pinfunction "VSS_PAD_P$83") (pintype "bidirectional"))
      (node (ref "U1") (pin "P$84") (pinfunction "VSS_PAD_P$84") (pintype "bidirectional"))
      (node (ref "U1") (pin "P$85") (pinfunction "VSS_PAD_P$85") (pintype "bidirectional"))
      (node (ref "U1") (pin "P$86") (pinfunction "VSS_PAD_P$86") (pintype "bidirectional"))
      (node (ref "U1") (pin "P$87") (pinfunction "VSS_PAD_P$87") (pintype "bidirectional"))
      (node (ref "U1") (pin "P$88") (pinfunction "VSS_PAD_P$88") (pintype "bidirectional"))
      (node (ref "U1") (pin "P$89") (pinfunction "VSS_PAD_P$89") (pintype "bidirectional"))
      (node (ref "U1") (pin "P$90") (pinfunction "VSS_PAD_P$90") (pintype "bidirectional"))
      (node (ref "U1") (pin "P$B7") (pinfunction "VSS_P$B7") (pintype "power_in"))
      (node (ref "U1") (pin "P$F23") (pinfunction "VSS_PA_P$F23") (pintype "bidirectional"))
      (node (ref "U3") (pin "1") (pinfunction "CTG_1") (pintype "power_in"))
      (node (ref "U3") (pin "4") (pinfunction "GND_4") (pintype "power_in"))
      (node (ref "U3") (pin "6") (pinfunction "QSTRT_6") (pintype "input"))
      (node (ref "U3") (pin "9") (pinfunction "EP_9") (pintype "power_in"))
      (node (ref "X1") (pin "2") (pinfunction "2_2") (pintype "passive"))
      (node (ref "X1") (pin "4") (pinfunction "4_4") (pintype "passive"))
    )
    (net (code "25") (name "HAPTIC_EN{slash}1.4C") (class "Default")
      (node (ref "IC2") (pin "A1") (pinfunction "EN_A1") (pintype "bidirectional"))
    )
    (net (code "26") (name "HAPTIC_EN{slash}2.6A") (class "Default")
      (node (ref "U1") (pin "P$U1") (pinfunction "P0.12_P$U1") (pintype "bidirectional"))
    )
    (net (code "27") (name "IMU_INT1") (class "Default")
      (node (ref "IC3") (pin "5") (pinfunction "INT1_5") (pintype "bidirectional"))
      (node (ref "U1") (pin "P$N1") (pinfunction "P0.08_P$N1") (pintype "bidirectional"))
    )
    (net (code "28") (name "IMU_INT2") (class "Default")
      (node (ref "IC3") (pin "6") (pinfunction "INT2_6") (pintype "bidirectional"))
      (node (ref "U1") (pin "P$P2") (pinfunction "P1.08_P$P2") (pintype "bidirectional"))
    )
    (net (code "29") (name "LX1") (class "Default")
      (node (ref "IC9") (pin "B2") (pinfunction "SW1_1_B2") (pintype "bidirectional"))
      (node (ref "IC9") (pin "B3") (pinfunction "SW1_2_B3") (pintype "bidirectional"))
      (node (ref "L7") (pin "1") (pinfunction "1_1") (pintype "bidirectional"))
    )
    (net (code "30") (name "LX2") (class "Default")
      (node (ref "IC9") (pin "D2") (pinfunction "SW2_1_D2") (pintype "bidirectional"))
      (node (ref "IC9") (pin "D3") (pinfunction "SW2_2_D3") (pintype "bidirectional"))
      (node (ref "L7") (pin "2") (pinfunction "2_2") (pintype "bidirectional"))
    )
    (net (code "31") (name "MOSI{slash}1.5B") (class "Default")
      (node (ref "J1") (pin "14") (pinfunction "14_14") (pintype "bidirectional"))
    )
    (net (code "32") (name "MOSI{slash}2.2D") (class "Default")
      (node (ref "U1") (pin "P$B13") (pinfunction "P0.03/AIN1_P$B13") (pintype "bidirectional"))
    )
    (net (code "33") (name "Net-(ANT1-FEED)") (class "Default")
      (node (ref "ANT1") (pin "1") (pinfunction "FEED_1") (pintype "input"))
      (node (ref "C22") (pin "1") (pinfunction "1_1") (pintype "passive"))
      (node (ref "C4") (pin "1") (pinfunction "1_1") (pintype "passive"))
      (node (ref "L1") (pin "2") (pinfunction "2_2") (pintype "passive"))
    )
    (net (code "34") (name "Net-(D2-K)") (class "Default")
      (node (ref "C2-EP-DR") (pin "1") (pinfunction "1_1") (pintype "passive"))
      (node (ref "D2") (pin "1") (pinfunction "K_1") (pintype "bidirectional"))
      (node (ref "D4") (pin "2") (pinfunction "A_2") (pintype "bidirectional"))
    )
    (net (code "35") (name "Net-(D5-A)") (class "Default")
      (node (ref "C2-EP-DR") (pin "2") (pinfunction "2_2") (pintype "passive"))
      (node (ref "D5") (pin "2") (pinfunction "A_2") (pintype "bidirectional"))
      (node (ref "L5") (pin "2") (pinfunction "2_2") (pintype "passive"))
      (node (ref "Q3") (pin "3") (pinfunction "D_3") (pintype "bidirectional"))
    )
    (net (code "36") (name "Net-(EPD_C1-Pad2)") (class "Default")
      (node (ref "EPD_C1") (pin "2") (pinfunction "2_2") (pintype "passive"))
      (node (ref "J1") (pin "5") (pinfunction "5_5") (pintype "bidirectional"))
    )
    (net (code "37") (name "Net-(EPD_C2-Pad2)") (class "Default")
      (node (ref "EPD_C2") (pin "2") (pinfunction "2_2") (pintype "passive"))
      (node (ref "J1") (pin "4") (pinfunction "4_4") (pintype "bidirectional"))
    )
    (net (code "38") (name "Net-(EPD_C6-Pad2)") (class "Default")
      (node (ref "EPD_C6") (pin "2") (pinfunction "2_2") (pintype "passive"))
      (node (ref "J1") (pin "18") (pinfunction "18_18") (pintype "bidirectional"))
    )
    (net (code "39") (name "Net-(EPD_C7-Pad2)") (class "Default")
      (node (ref "EPD_C7") (pin "2") (pinfunction "2_2") (pintype "passive"))
      (node (ref "J1") (pin "19") (pinfunction "19_19") (pintype "bidirectional"))
    )
    (net (code "40") (name "Net-(EPD_C8-Pad2)") (class "Default")
      (node (ref "EPD_C8") (pin "2") (pinfunction "2_2") (pintype "passive"))
      (node (ref "J1") (pin "20") (pinfunction "20_20") (pintype "bidirectional"))
    )
    (net (code "41") (name "Net-(EPD_C10-Pad2)") (class "Default")
      (node (ref "EPD_C10") (pin "2") (pinfunction "2_2") (pintype "passive"))
      (node (ref "J1") (pin "22") (pinfunction "22_22") (pintype "bidirectional"))
    )
    (net (code "42") (name "Net-(EPD_C12-Pad2)") (class "Default")
      (node (ref "EPD_C12") (pin "2") (pinfunction "2_2") (pintype "passive"))
      (node (ref "J1") (pin "24") (pinfunction "24_24") (pintype "bidirectional"))
    )
    (net (code "43") (name "Net-(IC1-TS{slash}MR)") (class "Default")
      (node (ref "IC1") (pin "D1") (pinfunction "TS/MR_D1") (pintype "bidirectional"))
      (node (ref "R9") (pin "2") (pinfunction "2_2") (pintype "bidirectional"))
    )
    (net (code "44") (name "Net-(IC2-REG)") (class "Default")
      (node (ref "C32") (pin "2") (pinfunction "2_2") (pintype "passive"))
      (node (ref "IC2") (pin "A2") (pinfunction "REG_A2") (pintype "bidirectional"))
    )
    (net (code "45") (name "Net-(IC3-SDO)") (class "Default")
      (node (ref "IC3") (pin "1") (pinfunction "SDO_1") (pintype "bidirectional"))
      (node (ref "R3") (pin "2") (pinfunction "2_2") (pintype "bidirectional"))
    )
    (net (code "46") (name "Net-(IC9-SCL)") (class "Default")
      (node (ref "IC9") (pin "D1") (pinfunction "SCL_D1") (pintype "bidirectional"))
      (node (ref "R4") (pin "2") (pinfunction "2_2") (pintype "bidirectional"))
    )
    (net (code "47") (name "Net-(IC9-SDA)") (class "Default")
      (node (ref "IC9") (pin "E1") (pinfunction "SDA_E1") (pintype "bidirectional"))
      (node (ref "R2") (pin "2") (pinfunction "2_2") (pintype "bidirectional"))
    )
    (net (code "48") (name "Net-(J4-CC1)") (class "Default")
      (node (ref "J4") (pin "A5") (pinfunction "CC1_A5") (pintype "bidirectional"))
      (node (ref "R1_USB") (pin "2") (pinfunction "2_2") (pintype "bidirectional"))
    )
    (net (code "49") (name "Net-(J4-CC2)") (class "Default")
      (node (ref "J4") (pin "B5") (pinfunction "CC2_B5") (pintype "bidirectional"))
      (node (ref "R2_USB") (pin "1") (pinfunction "1_1") (pintype "bidirectional"))
    )
    (net (code "50") (name "Net-(L2-Pad2)") (class "Default")
      (node (ref "L2") (pin "2") (pinfunction "2_2") (pintype "passive"))
      (node (ref "L3") (pin "1") (pinfunction "1_1") (pintype "passive"))
    )
    (net (code "51") (name "Net-(R1_EP_DR-Pad1)") (class "Default")
      (node (ref "R1_EP_DR") (pin "1") (pinfunction "1_1") (pintype "bidirectional"))
      (node (ref "R_TYPE_SEL") (pin "2") (pinfunction "2_2") (pintype "bidirectional"))
      (node (ref "SJ1") (pin "2") (pinfunction "2_2") (pintype "passive"))
    )
    (net (code "52") (name "Net-(U1-ANT)") (class "Default")
      (node (ref "C3") (pin "1") (pinfunction "1_1") (pintype "passive"))
      (node (ref "L1") (pin "1") (pinfunction "1_1") (pintype "passive"))
      (node (ref "U1") (pin "P$H23") (pinfunction "ANT_P$H23") (pintype "bidirectional"))
    )
    (net (code "53") (name "Net-(U1-DCC)") (class "Default")
      (node (ref "L2") (pin "1") (pinfunction "1_1") (pintype "passive"))
      (node (ref "U1") (pin "P$B3") (pinfunction "DCC_P$B3") (pintype "output"))
    )
    (net (code "54") (name "Net-(U1-DEC2)") (class "Default")
      (node (ref "C13") (pin "1") (pinfunction "1_1") (pintype "passive"))
      (node (ref "U1") (pin "P$A18") (pinfunction "DEC2_P$A18") (pintype "bidirectional"))
    )
    (net (code "55") (name "Net-(U1-DEC3V3)") (class "Default")
      (node (ref "C20") (pin "1") (pinfunction "1_1") (pintype "passive"))
      (node (ref "U1") (pin "P$AC5") (pinfunction "DEC3V3_P$AC5") (pintype "bidirectional"))
    )
    (net (code "56") (name "Net-(U1-DEC5)") (class "Default")
      (node (ref "C9") (pin "1") (pinfunction "1_1") (pintype "passive"))
      (node (ref "U1") (pin "P$N24") (pinfunction "DEC5_P$N24") (pintype "bidirectional"))
    )
    (net (code "57") (name "Net-(U1-XC1)") (class "Default")
      (node (ref "C1") (pin "1") (pinfunction "1_1") (pintype "passive"))
      (node (ref "U1") (pin "P$B24") (pinfunction "XC1_P$B24") (pintype "input"))
      (node (ref "X1") (pin "1") (pinfunction "1_1") (pintype "passive"))
    )
    (net (code "58") (name "Net-(U1-XC2)") (class "Default")
      (node (ref "C2") (pin "1") (pinfunction "1_1") (pintype "passive"))
      (node (ref "U1") (pin "P$A23") (pinfunction "XC2_P$A23") (pintype "output"))
      (node (ref "X1") (pin "3") (pinfunction "3_3") (pintype "passive"))
    )
    (net (code "59") (name "OUT+") (class "Default")
      (node (ref "IC2") (pin "A3") (pinfunction "OUT+_A3") (pintype "bidirectional"))
      (node (ref "TP_OP") (pin "TP") (pinfunction "TP_TP") (pintype "input"))
    )
    (net (code "60") (name "OUT-") (class "Default")
      (node (ref "IC2") (pin "C3") (pinfunction "OUT-_C3") (pintype "bidirectional"))
      (node (ref "TP_ON") (pin "TP") (pinfunction "TP_TP") (pintype "input"))
    )
    (net (code "61") (name "P0.00{slash}XL1") (class "Default")
      (node (ref "C17") (pin "2") (pinfunction "2_2") (pintype "passive"))
      (node (ref "U1") (pin "P$D2") (pinfunction "P0.00/XL1_P$D2") (pintype "bidirectional"))
      (node (ref "X2") (pin "1") (pinfunction "1_1") (pintype "passive"))
    )
    (net (code "62") (name "P0.01{slash}XL2") (class "Default")
      (node (ref "C18") (pin "2") (pinfunction "2_2") (pintype "passive"))
      (node (ref "U1") (pin "P$F2") (pinfunction "P0.01/XL2_P$F2") (pintype "bidirectional"))
      (node (ref "X2") (pin "2") (pinfunction "2_2") (pintype "passive"))
    )
    (net (code "63") (name "P0.04") (class "Default")
      (node (ref "U1") (pin "P$J1") (pinfunction "P0.04/AIN2_P$J1") (pintype "bidirectional"))
    )
    (net (code "64") (name "P0.09") (class "Default")
      (node (ref "U1") (pin "P$L24") (pinfunction "P0.09/NFC1_P$L24") (pintype "bidirectional"))
    )
    (net (code "65") (name "P0.13{slash}1.5D") (class "Default")
      (node (ref "C30") (pin "2") (pinfunction "2_2") (pintype "passive"))
      (node (ref "R5") (pin "1") (pinfunction "1_1") (pintype "bidirectional"))
      (node (ref "SW_UP") (pin "2") (pinfunction "2_2") (pintype "passive"))
    )
    (net (code "66") (name "P0.13{slash}2.6C") (class "Default")
      (node (ref "U1") (pin "P$AD8") (pinfunction "P0.13_P$AD8") (pintype "bidirectional"))
    )
    (net (code "67") (name "P0.14{slash}1.5D") (class "Default")
      (node (ref "C31") (pin "2") (pinfunction "2_2") (pintype "passive"))
      (node (ref "R8") (pin "1") (pinfunction "1_1") (pintype "bidirectional"))
      (node (ref "SW_ENT") (pin "2") (pinfunction "2_2") (pintype "passive"))
    )
    (net (code "68") (name "P0.14{slash}2.7C") (class "Default")
      (node (ref "U1") (pin "P$AC9") (pinfunction "P0.14_P$AC9") (pintype "bidirectional"))
    )
    (net (code "69") (name "P0.19") (class "Default")
      (node (ref "U1") (pin "P$AC15") (pinfunction "P0.19_P$AC15") (pintype "bidirectional"))
    )
    (net (code "70") (name "P0.20") (class "Default")
      (node (ref "U1") (pin "P$AD16") (pinfunction "P0.20_P$AD16") (pintype "bidirectional"))
    )
    (net (code "71") (name "P0.21") (class "Default")
      (node (ref "U1") (pin "P$AC17") (pinfunction "P0.21_P$AC17") (pintype "bidirectional"))
    )
    (net (code "72") (name "P0.22") (class "Default")
      (node (ref "U1") (pin "P$AD18") (pinfunction "P0.22_P$AD18") (pintype "bidirectional"))
    )
    (net (code "73") (name "P0.23") (class "Default")
      (node (ref "U1") (pin "P$AC19") (pinfunction "P0.23_P$AC19") (pintype "bidirectional"))
    )
    (net (code "74") (name "P0.24") (class "Default")
      (node (ref "U1") (pin "P$AD20") (pinfunction "P0.24_P$AD20") (pintype "bidirectional"))
    )
    (net (code "75") (name "P0.25") (class "Default")
      (node (ref "U1") (pin "P$AC21") (pinfunction "P0.25_P$AC21") (pintype "bidirectional"))
    )
    (net (code "76") (name "P0.26") (class "Default")
      (node (ref "U1") (pin "P$G1") (pinfunction "P0.26_P$G1") (pintype "bidirectional"))
    )
    (net (code "77") (name "P0.27") (class "Default")
      (node (ref "U1") (pin "P$H2") (pinfunction "P0.27_P$H2") (pintype "bidirectional"))
    )
    (net (code "78") (name "P0.28") (class "Default")
      (node (ref "U1") (pin "P$B11") (pinfunction "P0.28/AIN4_P$B11") (pintype "bidirectional"))
    )
    (net (code "79") (name "P0.29") (class "Default")
      (node (ref "U1") (pin "P$A10") (pinfunction "P0.29/AIN5_P$A10") (pintype "bidirectional"))
    )
    (net (code "80") (name "P0.30") (class "Default")
      (node (ref "U1") (pin "P$B9") (pinfunction "P0.30/AIN6_P$B9") (pintype "bidirectional"))
    )
    (net (code "81") (name "P0.31") (class "Default")
      (node (ref "U1") (pin "P$A8") (pinfunction "P0.31/AIN7_P$A8") (pintype "bidirectional"))
    )
    (net (code "82") (name "P1.01{slash}1.6C") (class "Default")
      (node (ref "DMG2305UX-7") (pin "1") (pinfunction "G_1") (pintype "bidirectional"))
      (node (ref "R_PWR_EPD") (pin "1") (pinfunction "1_1") (pintype "bidirectional"))
    )
    (net (code "83") (name "P1.01{slash}2.4B") (class "Default")
      (node (ref "U1") (pin "P$Y23") (pinfunction "P1.01_P$Y23") (pintype "bidirectional"))
    )
    (net (code "84") (name "P1.02{slash}1.6C") (class "Default")
      (node (ref "C29") (pin "2") (pinfunction "2_2") (pintype "passive"))
      (node (ref "R7") (pin "1") (pinfunction "1_1") (pintype "bidirectional"))
      (node (ref "SW_DN") (pin "2") (pinfunction "2_2") (pintype "passive"))
    )
    (net (code "85") (name "P1.02{slash}2.8C") (class "Default")
      (node (ref "U1") (pin "P$W24") (pinfunction "P1.02_P$W24") (pintype "bidirectional"))
    )
    (net (code "86") (name "P1.03") (class "Default")
      (node (ref "U1") (pin "P$V23") (pinfunction "P1.03_P$V23") (pintype "bidirectional"))
    )
    (net (code "87") (name "P1.04") (class "Default")
      (node (ref "U1") (pin "P$U24") (pinfunction "P1.04_P$U24") (pintype "bidirectional"))
    )
    (net (code "88") (name "P1.05") (class "Default")
      (node (ref "U1") (pin "P$T23") (pinfunction "P1.05_P$T23") (pintype "bidirectional"))
    )
    (net (code "89") (name "P1.06") (class "Default")
      (node (ref "U1") (pin "P$R24") (pinfunction "P1.06_P$R24") (pintype "bidirectional"))
    )
    (net (code "90") (name "P1.07") (class "Default")
      (node (ref "U1") (pin "P$P23") (pinfunction "P1.07_P$P23") (pintype "bidirectional"))
    )
    (net (code "91") (name "P1.09") (class "Default")
      (node (ref "U1") (pin "P$R1") (pinfunction "P1.09_P$R1") (pintype "bidirectional"))
    )
    (net (code "92") (name "P1.10") (class "Default")
      (node (ref "U1") (pin "P$A20") (pinfunction "P1.10_P$A20") (pintype "bidirectional"))
    )
    (net (code "93") (name "P1.11") (class "Default")
      (node (ref "U1") (pin "P$B19") (pinfunction "P1.11_P$B19") (pintype "bidirectional"))
    )
    (net (code "94") (name "P1.12") (class "Default")
      (node (ref "U1") (pin "P$B17") (pinfunction "P1.12_P$B17") (pintype "bidirectional"))
    )
    (net (code "95") (name "P1.13") (class "Default")
      (node (ref "U1") (pin "P$A16") (pinfunction "P1.13_P$A16") (pintype "bidirectional"))
    )
    (net (code "96") (name "P1.14") (class "Default")
      (node (ref "U1") (pin "P$B15") (pinfunction "P1.14_P$B15") (pintype "bidirectional"))
    )
    (net (code "97") (name "P1.15") (class "Default")
      (node (ref "U1") (pin "P$A14") (pinfunction "P1.15_P$A14") (pintype "bidirectional"))
    )
    (net (code "98") (name "PMIC_INT") (class "Default")
      (node (ref "IC1") (pin "A1") (pinfunction "~{INT}_A1") (pintype "bidirectional"))
      (node (ref "U1") (pin "P$T2") (pinfunction "P0.11_P$T2") (pintype "bidirectional"))
    )
    (net (code "99") (name "PREVGH") (class "Default")
      (node (ref "D5") (pin "1") (pinfunction "K_1") (pintype "bidirectional"))
      (node (ref "EPD_C9") (pin "2") (pinfunction "2_2") (pintype "passive"))
      (node (ref "J1") (pin "21") (pinfunction "21_21") (pintype "bidirectional"))
    )
    (net (code "100") (name "PREVGL") (class "Default")
      (node (ref "D2") (pin "2") (pinfunction "A_2") (pintype "bidirectional"))
      (node (ref "EPD_C11") (pin "2") (pinfunction "2_2") (pintype "passive"))
      (node (ref "J1") (pin "23") (pinfunction "23_23") (pintype "bidirectional"))
    )
    (net (code "101") (name "RESE") (class "Default")
      (node (ref "J1") (pin "3") (pinfunction "3_3") (pintype "bidirectional"))
      (node (ref "Q3") (pin "2") (pinfunction "S_2") (pintype "bidirectional"))
      (node (ref "R1_EP_DR") (pin "2") (pinfunction "2_2") (pintype "bidirectional"))
    )
    (net (code "102") (name "RESET") (class "Default")
      (node (ref "J2") (pin "6") (pinfunction "6_6") (pintype "bidirectional"))
      (node (ref "TP_RESET") (pin "TP") (pinfunction "TP_TP") (pintype "input"))
      (node (ref "U1") (pin "P$AC13") (pinfunction "P0.18/RESET_P$AC13") (pintype "bidirectional"))
    )
    (net (code "103") (name "SCK{slash}1.5B") (class "Default")
      (node (ref "J1") (pin "13") (pinfunction "13_13") (pintype "bidirectional"))
    )
    (net (code "104") (name "SCK{slash}2.2D") (class "Default")
      (node (ref "U1") (pin "P$A12") (pinfunction "P0.02/AIN0_P$A12") (pintype "bidirectional"))
    )
    (net (code "105") (name "SCL{slash}1.4C") (class "Default")
      (node (ref "IC2") (pin "C1") (pinfunction "SCL_C1") (pintype "bidirectional"))
      (node (ref "U3") (pin "7") (pinfunction "SCL_7") (pintype "input"))
    )
    (net (code "106") (name "SCL{slash}2.4C") (class "Default")
      (node (ref "IC1") (pin "B1") (pinfunction "SCL_B1") (pintype "bidirectional"))
      (node (ref "IC3") (pin "12") (pinfunction "SCX_12") (pintype "bidirectional"))
      (node (ref "R17") (pin "2") (pinfunction "2_2") (pintype "bidirectional"))
      (node (ref "R4") (pin "1") (pinfunction "1_1") (pintype "bidirectional"))
      (node (ref "TP_SCL") (pin "TP") (pinfunction "TP_TP") (pintype "input"))
      (node (ref "U1") (pin "P$M2") (pinfunction "P0.07_P$M2") (pintype "bidirectional"))
    )
    (net (code "107") (name "SDA{slash}1.4C") (class "Default")
      (node (ref "IC2") (pin "B2") (pinfunction "SDA_B2") (pintype "bidirectional"))
      (node (ref "U3") (pin "8") (pinfunction "SDA_8") (pintype "bidirectional"))
    )
    (net (code "108") (name "SDA{slash}2.4C") (class "Default")
      (node (ref "IC1") (pin "C1") (pinfunction "SDA_C1") (pintype "bidirectional"))
      (node (ref "IC3") (pin "2") (pinfunction "SDX_2") (pintype "bidirectional"))
      (node (ref "R18") (pin "2") (pinfunction "2_2") (pintype "bidirectional"))
      (node (ref "R2") (pin "1") (pinfunction "1_1") (pintype "bidirectional"))
      (node (ref "TP_SDA") (pin "TP") (pinfunction "TP_TP") (pintype "input"))
      (node (ref "U1") (pin "P$L1") (pinfunction "P0.06_P$L1") (pintype "bidirectional"))
    )
    (net (code "109") (name "SWDCLK") (class "Default")
      (node (ref "J2") (pin "4") (pinfunction "4_4") (pintype "bidirectional"))
      (node (ref "TP_SWDCLK") (pin "TP") (pinfunction "TP_TP") (pintype "input"))
      (node (ref "U1") (pin "P$AA24") (pinfunction "SWDCLK_P$AA24") (pintype "input"))
    )
    (net (code "110") (name "SWDIO") (class "Default")
      (node (ref "J2") (pin "2") (pinfunction "2_2") (pintype "bidirectional"))
      (node (ref "TP_SWDIO") (pin "TP") (pinfunction "TP_TP") (pintype "input"))
      (node (ref "U1") (pin "P$AC24") (pinfunction "SWDIO_P$AC24") (pintype "bidirectional"))
    )
    (net (code "111") (name "SWO") (class "Default")
      (node (ref "TP_SWO") (pin "TP") (pinfunction "TP_TP") (pintype "input"))
      (node (ref "U1") (pin "P$AD22") (pinfunction "P1.00_P$AD22") (pintype "bidirectional"))
    )
    (net (code "112") (name "VBAT{slash}1.2A") (class "Default")
      (node (ref "C27") (pin "2") (pinfunction "2_2") (pintype "passive"))
      (node (ref "TP_VBAT") (pin "TP") (pinfunction "TP_TP") (pintype "input"))
      (node (ref "U3") (pin "2") (pinfunction "CELL_2") (pintype "power_in"))
      (node (ref "U3") (pin "3") (pinfunction "VDD_3") (pintype "power_in"))
    )
    (net (code "113") (name "VBAT{slash}2.5C") (class "Default")
      (node (ref "C37") (pin "1") (pinfunction "1_1") (pintype "passive"))
      (node (ref "IC1") (pin "C2") (pinfunction "BAT_C2") (pintype "bidirectional"))
    )
    (net (code "114") (name "VBUS{slash}1.5D") (class "Default")
      (node (ref "C42") (pin "1") (pinfunction "1_1") (pintype "passive"))
      (node (ref "C43") (pin "1") (pinfunction "1_1") (pintype "passive"))
      (node (ref "D3") (pin "5") (pinfunction "VBUS_5") (pintype "bidirectional"))
      (node (ref "J4") (pin "A4_B9") (pinfunction "VBUS_A4_B9") (pintype "power_in"))
      (node (ref "J4") (pin "A9_B4") (pinfunction "VBUS_A9_B4") (pintype "power_in"))
    )
    (net (code "115") (name "VBUS{slash}2.6D") (class "Default")
      (node (ref "C21") (pin "1") (pinfunction "1_1") (pintype "passive"))
      (node (ref "C38") (pin "1") (pinfunction "1_1") (pintype "passive"))
      (node (ref "IC1") (pin "A2") (pinfunction "IN_A2") (pintype "bidirectional"))
      (node (ref "U1") (pin "P$AD2") (pinfunction "VBUS_P$AD2") (pintype "power_in"))
    )
    (net (code "116") (name "VREG") (class "Default")
      (node (ref "C23") (pin "1") (pinfunction "1_1") (pintype "passive"))
      (node (ref "C24") (pin "2") (pinfunction "2_2") (pintype "passive"))
      (node (ref "C39") (pin "1") (pinfunction "1_1") (pintype "passive"))
      (node (ref "IC1") (pin "B2") (pinfunction "SYS_B2") (pintype "bidirectional"))
      (node (ref "IC9") (pin "A1") (pinfunction "EN_A1") (pintype "bidirectional"))
      (node (ref "IC9") (pin "A2") (pinfunction "VIN_1_A2") (pintype "bidirectional"))
      (node (ref "IC9") (pin "A3") (pinfunction "VIN_2_A3") (pintype "bidirectional"))
      (node (ref "TP_VREG") (pin "TP") (pinfunction "TP_TP") (pintype "input"))
    )
    (net (code "117") (name "unconnected-(ANT1-NC-Pad2)") (class "Default")
      (node (ref "ANT1") (pin "2") (pinfunction "NC_2") (pintype "no_connect"))
    )
    (net (code "118") (name "unconnected-(IC3-ASCL-Pad11)") (class "Default")
      (node (ref "IC3") (pin "11") (pinfunction "ASCL_11") (pintype "bidirectional"))
    )
    (net (code "119") (name "unconnected-(IC3-ASDA-Pad4)") (class "Default")
      (node (ref "IC3") (pin "4") (pinfunction "ASDA_4") (pintype "bidirectional"))
    )
    (net (code "120") (name "unconnected-(J1-Pad1)") (class "Default")
      (node (ref "J1") (pin "1") (pinfunction "1_1") (pintype "bidirectional"))
    )
    (net (code "121") (name "unconnected-(J1-Pad6)") (class "Default")
      (node (ref "J1") (pin "6") (pinfunction "6_6") (pintype "bidirectional"))
    )
    (net (code "122") (name "unconnected-(J1-Pad7)") (class "Default")
      (node (ref "J1") (pin "7") (pinfunction "7_7") (pintype "bidirectional"))
    )
    (net (code "123") (name "unconnected-(J4-SBU1-PadA8)") (class "Default")
      (node (ref "J4") (pin "A8") (pinfunction "SBU1_A8") (pintype "bidirectional"))
    )
    (net (code "124") (name "unconnected-(J4-SBU2-PadB8)") (class "Default")
      (node (ref "J4") (pin "B8") (pinfunction "SBU2_B8") (pintype "bidirectional"))
    )
    (net (code "125") (name "unconnected-(U1-DCCH-PadP$AB2)") (class "Default")
      (node (ref "U1") (pin "P$AB2") (pinfunction "DCCH_P$AB2") (pintype "bidirectional"))
    )
  )
)
